# Sheet1.net
KiCad netlist of a schematic drawn in Altium Designer
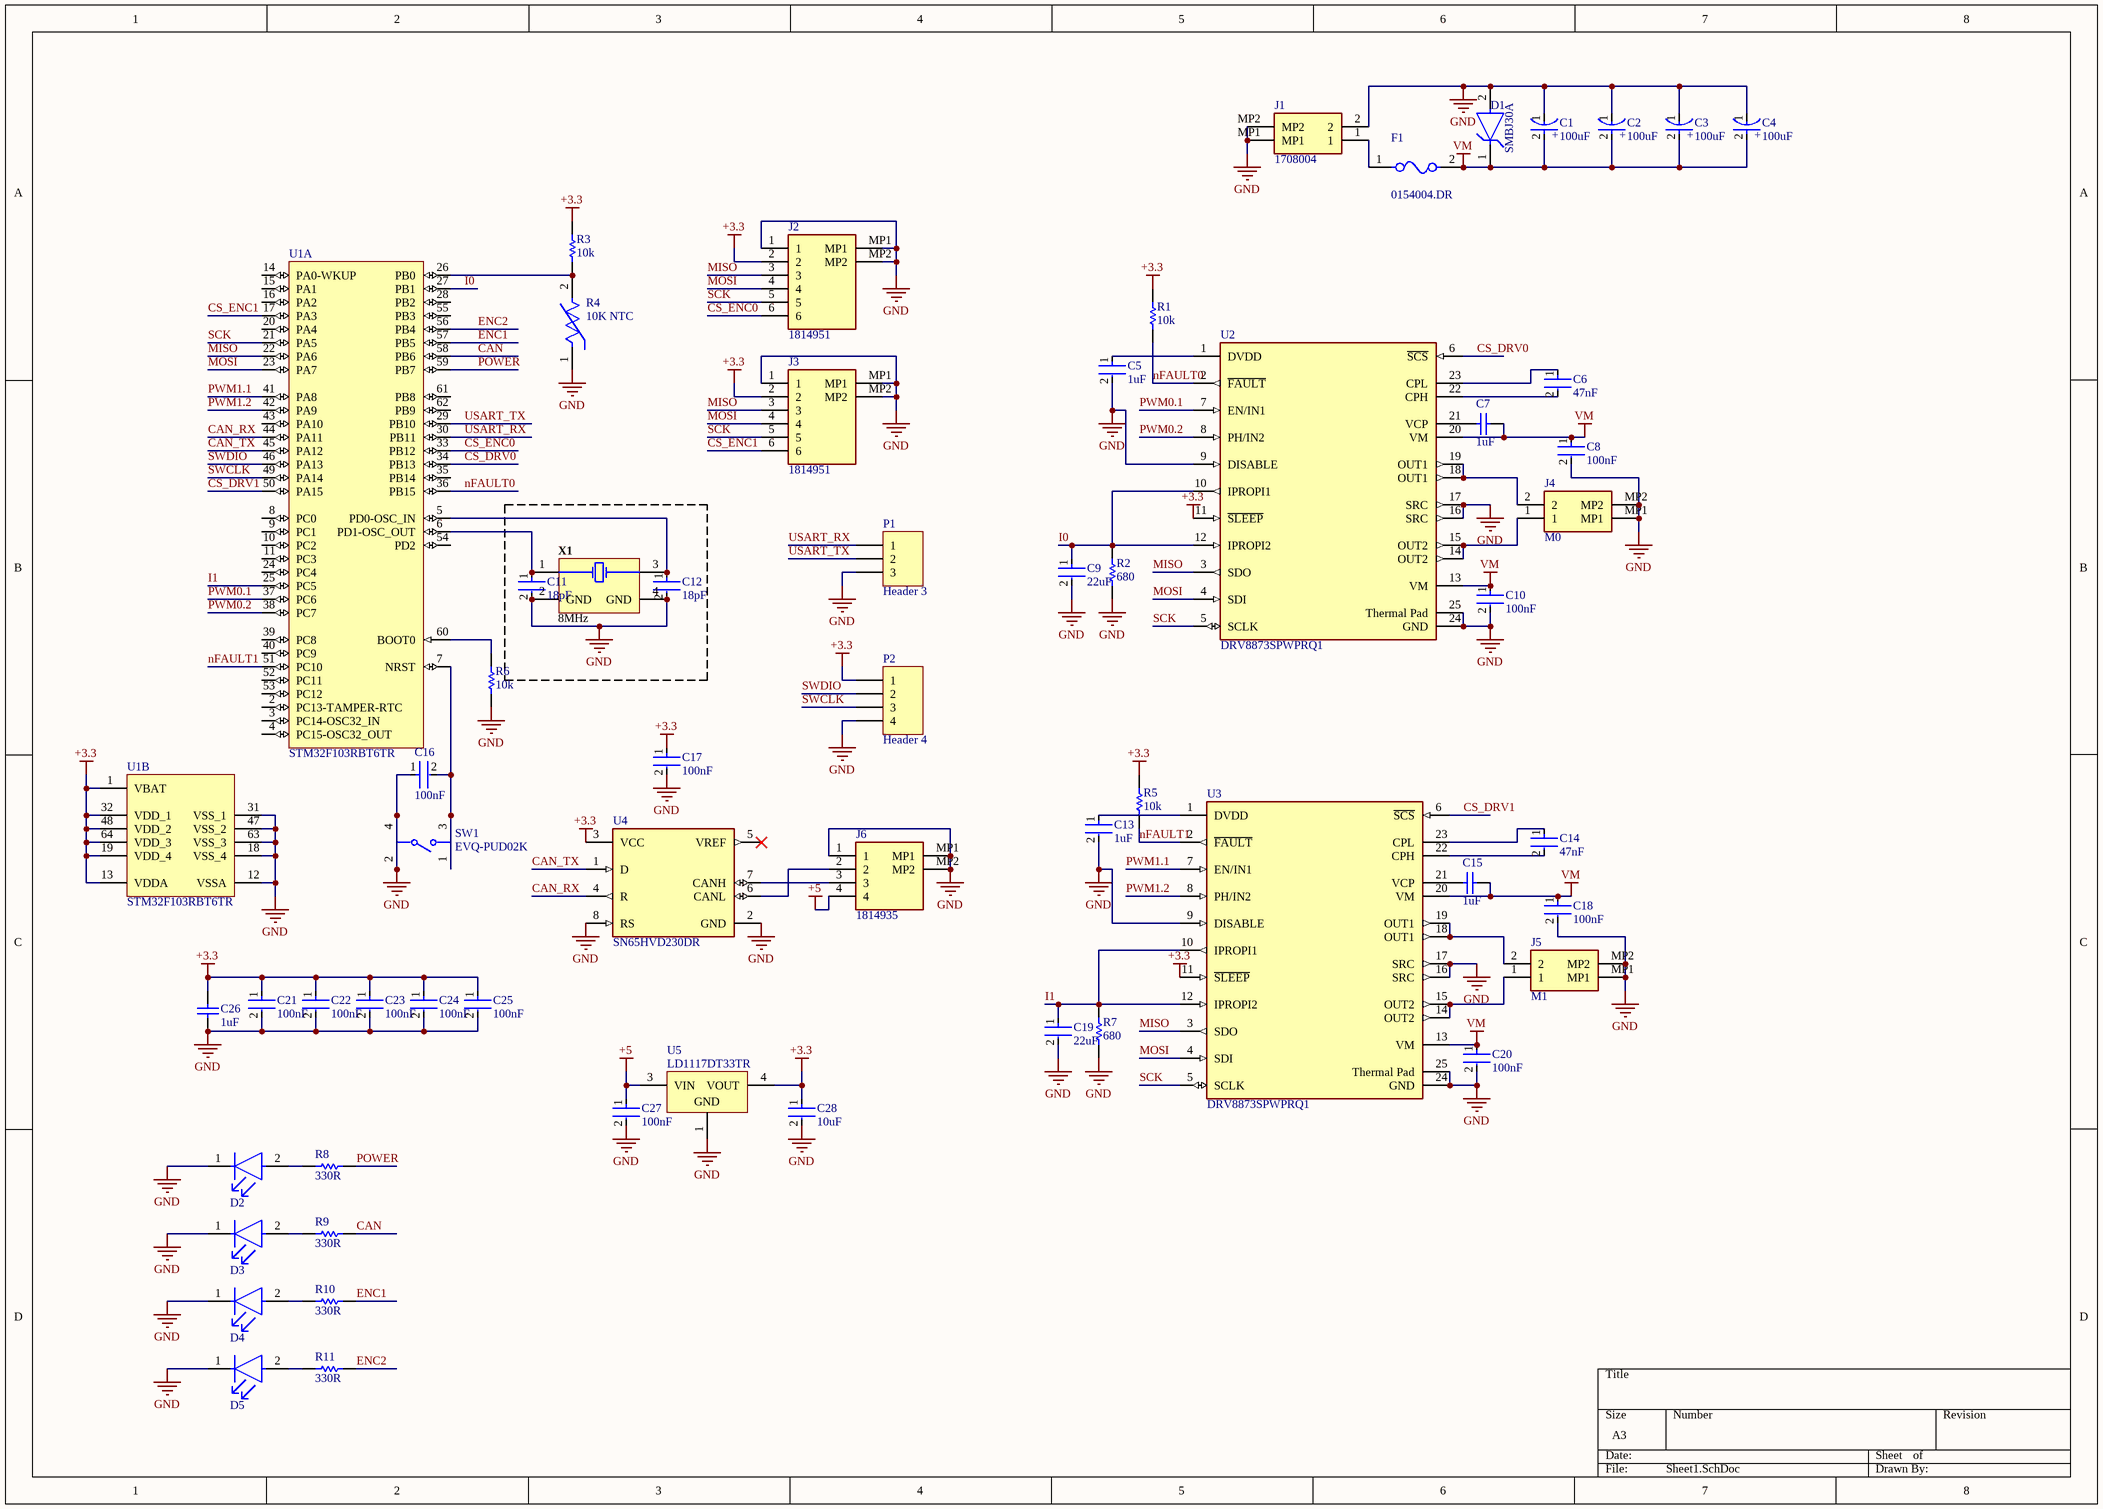
[diagram p0: Sheet1.SchDoc]

(export (version "E")
  (design (tool "Eeschema 10.0.6"))
  (components
    (comp (ref "C1")
      (value "100uF")
      (footprint "FP-FTD-MFG")
      (description "CAP ALUM 100UF 20% 35V SMD")
      (fields (field (name "VOLTAGE") "35V") (field (name "TOLERANCE") "20%"))
      (libsource (lib "Altium Content Vault") (part "a00bbbee19879c290e62620ae7e47b1"))
    )
    (comp (ref "C2")
      (value "100uF")
      (footprint "FP-FTD-MFG")
      (description "CAP ALUM 100UF 20% 35V SMD")
      (fields (field (name "VOLTAGE") "35V") (field (name "TOLERANCE") "20%"))
      (libsource (lib "Altium Content Vault") (part "a00bbbee19879c290e62620ae7e47b1"))
    )
    (comp (ref "C3")
      (value "100uF")
      (footprint "FP-FTD-MFG")
      (description "CAP ALUM 100UF 20% 35V SMD")
      (fields (field (name "VOLTAGE") "35V") (field (name "TOLERANCE") "20%"))
      (libsource (lib "Altium Content Vault") (part "a00bbbee19879c290e62620ae7e47b1"))
    )
    (comp (ref "C4")
      (value "100uF")
      (footprint "FP-FTD-MFG")
      (description "CAP ALUM 100UF 20% 35V SMD")
      (fields (field (name "VOLTAGE") "35V") (field (name "TOLERANCE") "20%"))
      (libsource (lib "Altium Content Vault") (part "a00bbbee19879c290e62620ae7e47b1"))
    )
    (comp (ref "C5")
      (value "1uF")
      (footprint "FP-0805-L_2_01_0_2-W_1_25-IPC_B")
      (description "General Purpose Ceramic Capacitor, 0805, 100nF, 10%, X7R, 15%, 100V")
      (fields (field (name "VOLTAGE") "100V") (field (name "TOLERANCE") "10%"))
      (libsource (lib "Altium Content Vault") (part "b4654b650e69147ec39a6b967a45e02"))
    )
    (comp (ref "C6")
      (value "47nF")
      (footprint "FP-C0805C-DN-IPC_A")
      (description "CAP CER 0.047UF 50V X7R 0805")
      (fields
        (field (name "MANUFACTURER PART NUMBER") "C0805C473K5RACTU")
        (field (name "OCTOPART") "https://octopart.com/c0805c473k5ractu-kemet-138387")
      )
      (libsource (lib "Altium Content Vault") (part "b4654b650e69147ec39a6b967a45e02"))
    )
    (comp (ref "C7")
      (value "1uF")
      (footprint "CAPC2013X145X50ML20T25")
      (fields (field (name "MANUFACTURER") "Kemet") (field (name "PART NUMBER") "C0805C105K4PACTU"))
      (libsource (lib "Altium Content Vault") (part "CAP"))
    )
    (comp (ref "C8")
      (value "100nF")
      (footprint "FP-0805-L_2_01_0_2-W_1_25-MFG")
      (description "General Purpose Ceramic Capacitor, 0805, 100nF, 10%, X7R, 15%, 100V")
      (fields (field (name "VOLTAGE") "100V") (field (name "TOLERANCE") "10%"))
      (libsource (lib "Altium Content Vault") (part "b4654b650e69147ec39a6b967a45e02"))
    )
    (comp (ref "C9")
      (value "22uF")
      (footprint "FP-0805-L_2_01_0_2-W_1_25-IPC_B")
      (description "General Purpose Ceramic Capacitor, 0805, 100nF, 10%, X7R, 15%, 100V")
      (fields (field (name "VOLTAGE") "100V") (field (name "TOLERANCE") "10%"))
      (libsource (lib "Altium Content Vault") (part "b4654b650e69147ec39a6b967a45e02"))
    )
    (comp (ref "C10")
      (value "100nF")
      (footprint "FP-0805-L_2_01_0_2-W_1_25-MFG")
      (description "General Purpose Ceramic Capacitor, 0805, 100nF, 10%, X7R, 15%, 100V")
      (fields (field (name "VOLTAGE") "100V") (field (name "TOLERANCE") "10%"))
      (libsource (lib "Altium Content Vault") (part "b4654b650e69147ec39a6b967a45e02"))
    )
    (comp (ref "C11")
      (value "18pF")
      (footprint "FP-C0603C-CF-MFG")
      (description "CAP CER 18PF 100V 5% NP0 0603")
      (fields (field (name "TOLERANCE") "0.05") (field (name "MANUFACTURER") "KEMET"))
      (libsource (lib "Altium Content Vault") (part "b4654b650e69147ec39a6b967a45e02"))
    )
    (comp (ref "C12")
      (value "18pF")
      (footprint "FP-C0603C-CF-MFG")
      (description "CAP CER 18PF 100V 5% NP0 0603")
      (fields (field (name "TOLERANCE") "0.05") (field (name "MANUFACTURER") "KEMET"))
      (libsource (lib "Altium Content Vault") (part "b4654b650e69147ec39a6b967a45e02"))
    )
    (comp (ref "C13")
      (value "1uF")
      (footprint "FP-0805-L_2_01_0_2-W_1_25-IPC_B")
      (description "General Purpose Ceramic Capacitor, 0805, 100nF, 10%, X7R, 15%, 100V")
      (fields (field (name "VOLTAGE") "100V") (field (name "TOLERANCE") "10%"))
      (libsource (lib "Altium Content Vault") (part "b4654b650e69147ec39a6b967a45e02"))
    )
    (comp (ref "C14")
      (value "47nF")
      (footprint "FP-C0805C-DN-IPC_A")
      (description "CAP CER 0.047UF 50V X7R 0805")
      (fields
        (field (name "MANUFACTURER PART NUMBER") "C0805C473K5RACTU")
        (field (name "OCTOPART") "https://octopart.com/c0805c473k5ractu-kemet-138387")
      )
      (libsource (lib "Altium Content Vault") (part "b4654b650e69147ec39a6b967a45e02"))
    )
    (comp (ref "C15")
      (value "1uF")
      (footprint "CAPC2013X145X50ML20T25")
      (fields (field (name "MANUFACTURER") "Kemet") (field (name "PART NUMBER") "C0805C105K4PACTU"))
      (libsource (lib "Altium Content Vault") (part "CAP"))
    )
    (comp (ref "C16")
      (value "100nF")
      (footprint "FP-0805-L_2_01_0_2-W_1_25-IPC_B")
      (description "General Purpose Ceramic Capacitor, 0805, 100nF, 10%, X7R, 15%, 100V")
      (fields (field (name "VOLTAGE") "100V") (field (name "TOLERANCE") "10%"))
      (libsource (lib "Altium Content Vault") (part "b4654b650e69147ec39a6b967a45e02"))
    )
    (comp (ref "C17")
      (value "100nF")
      (footprint "FP-0805-L_2_01_0_2-W_1_25-MFG")
      (description "General Purpose Ceramic Capacitor, 0805, 100nF, 10%, X7R, 15%, 100V")
      (fields (field (name "VOLTAGE") "100V") (field (name "TOLERANCE") "10%"))
      (libsource (lib "Altium Content Vault") (part "b4654b650e69147ec39a6b967a45e02"))
    )
    (comp (ref "C18")
      (value "100nF")
      (footprint "FP-0805-L_2_01_0_2-W_1_25-MFG")
      (description "General Purpose Ceramic Capacitor, 0805, 100nF, 10%, X7R, 15%, 100V")
      (fields (field (name "VOLTAGE") "100V") (field (name "TOLERANCE") "10%"))
      (libsource (lib "Altium Content Vault") (part "b4654b650e69147ec39a6b967a45e02"))
    )
    (comp (ref "C19")
      (value "22uF")
      (footprint "FP-0805-L_2_01_0_2-W_1_25-IPC_B")
      (description "General Purpose Ceramic Capacitor, 0805, 100nF, 10%, X7R, 15%, 100V")
      (fields (field (name "VOLTAGE") "100V") (field (name "TOLERANCE") "10%"))
      (libsource (lib "Altium Content Vault") (part "b4654b650e69147ec39a6b967a45e02"))
    )
    (comp (ref "C20")
      (value "100nF")
      (footprint "FP-0805-L_2_01_0_2-W_1_25-MFG")
      (description "General Purpose Ceramic Capacitor, 0805, 100nF, 10%, X7R, 15%, 100V")
      (fields (field (name "VOLTAGE") "100V") (field (name "TOLERANCE") "10%"))
      (libsource (lib "Altium Content Vault") (part "b4654b650e69147ec39a6b967a45e02"))
    )
    (comp (ref "C21")
      (value "100nF")
      (footprint "FP-0805-L_2_01_0_2-W_1_25-IPC_B")
      (description "General Purpose Ceramic Capacitor, 0805, 100nF, 10%, X7R, 15%, 100V")
      (fields (field (name "VOLTAGE") "100V") (field (name "TOLERANCE") "10%"))
      (libsource (lib "Altium Content Vault") (part "b4654b650e69147ec39a6b967a45e02"))
    )
    (comp (ref "C22")
      (value "100nF")
      (footprint "FP-0805-L_2_01_0_2-W_1_25-IPC_B")
      (description "General Purpose Ceramic Capacitor, 0805, 100nF, 10%, X7R, 15%, 100V")
      (fields (field (name "VOLTAGE") "100V") (field (name "TOLERANCE") "10%"))
      (libsource (lib "Altium Content Vault") (part "b4654b650e69147ec39a6b967a45e02"))
    )
    (comp (ref "C23")
      (value "100nF")
      (footprint "FP-0805-L_2_01_0_2-W_1_25-IPC_B")
      (description "General Purpose Ceramic Capacitor, 0805, 100nF, 10%, X7R, 15%, 100V")
      (fields (field (name "VOLTAGE") "100V") (field (name "TOLERANCE") "10%"))
      (libsource (lib "Altium Content Vault") (part "b4654b650e69147ec39a6b967a45e02"))
    )
    (comp (ref "C24")
      (value "100nF")
      (footprint "FP-0805-L_2_01_0_2-W_1_25-IPC_B")
      (description "General Purpose Ceramic Capacitor, 0805, 100nF, 10%, X7R, 15%, 100V")
      (fields (field (name "VOLTAGE") "100V") (field (name "TOLERANCE") "10%"))
      (libsource (lib "Altium Content Vault") (part "b4654b650e69147ec39a6b967a45e02"))
    )
    (comp (ref "C25")
      (value "100nF")
      (footprint "FP-0805-L_2_01_0_2-W_1_25-IPC_B")
      (description "General Purpose Ceramic Capacitor, 0805, 100nF, 10%, X7R, 15%, 100V")
      (fields (field (name "VOLTAGE") "100V") (field (name "TOLERANCE") "10%"))
      (libsource (lib "Altium Content Vault") (part "b4654b650e69147ec39a6b967a45e02"))
    )
    (comp (ref "C26")
      (value "1uF")
      (footprint "CAPC2013X145X50ML20T25")
      (fields (field (name "MANUFACTURER") "Kemet") (field (name "PART NUMBER") "C0805C105K4PACTU"))
      (libsource (lib "Altium Content Vault") (part "CAP"))
    )
    (comp (ref "C27")
      (value "100nF")
      (footprint "FP-0805-L_2_01_0_2-W_1_25-IPC_B")
      (description "General Purpose Ceramic Capacitor, 0805, 100nF, 10%, X7R, 15%, 100V")
      (fields (field (name "VOLTAGE") "100V") (field (name "TOLERANCE") "10%"))
      (libsource (lib "Altium Content Vault") (part "b4654b650e69147ec39a6b967a45e02"))
    )
    (comp (ref "C28")
      (value "10uF")
      (footprint "FP-C0805C-DG-IPC_B")
      (description "CAP CER 10UF 10V X5R 0805")
      (fields (field (name "TOLERANCE") "10%") (field (name "MANUFACTURER PART NUMBER") "C0805C106K8PACTU"))
      (libsource (lib "Altium Content Vault") (part "11868f565c42a9108669ba33697ecf6"))
    )
    (comp (ref "D1")
      (value "SMBJ30A")
      (footprint "FP-SMBJ30A-E3-52-0")
      (description "TVS DIODE 30VWM 48.4VC DO214AA")
      (libsource (lib "Altium Content Vault") (part "d9da4cfb8af32e832502365dfa3d88e"))
    )
    (comp (ref "D2")
      (value "TLLG4401")
      (footprint "FP-6_544-5255_01-4-MFG")
      (description "TLLG4401 LED, Green, 2mcd, 3mmDia., T-1, +/-25deg, 565nm, 7mA, 1.9V Vf, 20V Vr, 20mW, -40")
      (libsource (lib "Altium Content Vault") (part "8706943c75ba83719d021d2fdc84c58"))
    )
    (comp (ref "D3")
      (value "TLLG4401")
      (footprint "FP-6_544-5255_01-4-MFG")
      (description "TLLG4401 LED, Green, 2mcd, 3mmDia., T-1, +/-25deg, 565nm, 7mA, 1.9V Vf, 20V Vr, 20mW, -40")
      (libsource (lib "Altium Content Vault") (part "8706943c75ba83719d021d2fdc84c58"))
    )
    (comp (ref "D4")
      (value "TLLG4401")
      (footprint "FP-6_544-5255_01-4-MFG")
      (description "TLLG4401 LED, Green, 2mcd, 3mmDia., T-1, +/-25deg, 565nm, 7mA, 1.9V Vf, 20V Vr, 20mW, -40")
      (libsource (lib "Altium Content Vault") (part "8706943c75ba83719d021d2fdc84c58"))
    )
    (comp (ref "D5")
      (value "TLLG4401")
      (footprint "FP-6_544-5255_01-4-MFG")
      (description "TLLG4401 LED, Green, 2mcd, 3mmDia., T-1, +/-25deg, 565nm, 7mA, 1.9V Vf, 20V Vr, 20mW, -40")
      (libsource (lib "Altium Content Vault") (part "8706943c75ba83719d021d2fdc84c58"))
    )
    (comp (ref "F1")
      (value "0154004.DR")
      (footprint "FP-0154-MFG")
      (description "FUSE BRD MNT 4A 125VAC/VDC 2SMD")
      (fields
        (field (name "MANUFACTURER") "Littelfuse")
        (field (name "OCTOPART") "https://octopart.com/0154004.dr-littelfuse-565861")
      )
      (libsource (lib "Altium Content Vault") (part "5bcf9b9f640e542cf0359d10258e979"))
    )
    (comp (ref "J1")
      (value "1708004")
      (footprint "1708004")
      (description "Pluggable Terminal Blocks PTSM 0,5/ 2-HH- 2,5-SMD WH R32")
      (fields (field (name "MOUSER PART NUMBER") "651-1708004"))
      (libsource (lib "1708004") (part "1708004"))
    )
    (comp (ref "J2")
      (value "1814951")
      (footprint "1814951")
      (description "Pluggable Terminal Blocks PTSM 0,5/ 6-HH0-2,5- SMD WH R44")
      (libsource (lib "1814951") (part "1814951"))
    )
    (comp (ref "J3")
      (value "1814951")
      (footprint "1814951")
      (description "Pluggable Terminal Blocks PTSM 0,5/ 6-HH0-2,5- SMD WH R44")
      (libsource (lib "1814951") (part "1814951"))
    )
    (comp (ref "J4")
      (value "M0")
      (footprint "1815125")
      (description "Phoenix Contact PTSM Series, 2.5mm Pitch Printed Circuit Board Connector, 6A")
      (fields
        (field (name "MOUSER PART NUMBER") "651-1815125")
        (field (name "MANUFACTURER_PART_NUMBER") "1815125")
      )
      (libsource (lib "1815125") (part "1815125"))
    )
    (comp (ref "J5")
      (value "M1")
      (footprint "1815125")
      (description "Phoenix Contact PTSM Series, 2.5mm Pitch Printed Circuit Board Connector, 6A")
      (fields
        (field (name "MOUSER PART NUMBER") "651-1815125")
        (field (name "MANUFACTURER_PART_NUMBER") "1815125")
      )
      (libsource (lib "1815125") (part "1815125"))
    )
    (comp (ref "J6")
      (value "1814935")
      (footprint "1814935")
      (description "Pluggable Terminal Blocks PTSM 0,5/ 4-HH0-2,5- SMD WH R32")
      (libsource (lib "1814935") (part "1814935"))
    )
    (comp (ref "P1")
      (value "Header 3")
      (footprint "HDR1X3")
      (description "Header, 3-Pin")
      (fields (field (name "PUBLISHER") "Altium Limited"))
      (libsource (lib "Miscellaneous Connectors") (part "Header 3"))
    )
    (comp (ref "P2")
      (value "Header 4")
      (footprint "HDR1X4")
      (description "Header, 4-Pin")
      (fields (field (name "PUBLISHER") "Altium Limited"))
      (libsource (lib "Miscellaneous Connectors") (part "Header 4"))
    )
    (comp (ref "R1")
      (value "10k")
      (footprint "RESC2013X60X35NL10T20")
      (description "Chip Resistor, 10 KOhm, +/- 1%, 0.125 W, -55 to 155 degC, 0805 (2012 Metric), RoHS, Tape and Reel")
      (fields (field (name "MANUFACTURER") "Yageo"))
      (libsource (lib "Altium Content Vault") (part "RES-2"))
    )
    (comp (ref "R2")
      (value "680")
      (footprint "RESC2013X60X35NL10T20")
      (description "Chip Resistor, 10 KOhm, +/- 1%, 0.125 W, -55 to 155 degC, 0805 (2012 Metric), RoHS, Tape and Reel")
      (fields (field (name "MANUFACTURER") "Yageo"))
      (libsource (lib "Altium Content Vault") (part "RES-2"))
    )
    (comp (ref "R3")
      (value "10k")
      (footprint "RESC2013X60X35ML10T20")
      (fields (field (name "TOLERANCE") "5%") (field (name "MANUFACTURER") "Yageo"))
      (libsource (lib "Altium Content Vault") (part "RES-2"))
    )
    (comp (ref "R4")
      (value "10K NTC")
      (footprint "FP-NCP18-0_15-IPC_A")
      (description "NTC Thermistor for Temperature Sensor, 0603, 10kΩ, 1%, 0.1mA, 5V")
      (fields (field (name "TOLERANCE") "1%"))
      (libsource (lib "Altium Content Vault") (part "3b148a6ebabc5fb4d708a66c052d352"))
    )
    (comp (ref "R5")
      (value "10k")
      (footprint "RESC2013X60X35NL10T20")
      (description "Chip Resistor, 10 KOhm, +/- 1%, 0.125 W, -55 to 155 degC, 0805 (2012 Metric), RoHS, Tape and Reel")
      (fields (field (name "MANUFACTURER") "Yageo"))
      (libsource (lib "Altium Content Vault") (part "RES-2"))
    )
    (comp (ref "R6")
      (value "10k")
      (footprint "RESC2013X60X35ML10T20")
      (fields (field (name "TOLERANCE") "5%") (field (name "MANUFACTURER") "Yageo"))
      (libsource (lib "Altium Content Vault") (part "RES-2"))
    )
    (comp (ref "R7")
      (value "680")
      (footprint "RESC2013X60X35NL10T20")
      (description "Chip Resistor, 10 KOhm, +/- 1%, 0.125 W, -55 to 155 degC, 0805 (2012 Metric), RoHS, Tape and Reel")
      (fields (field (name "MANUFACTURER") "Yageo"))
      (libsource (lib "Altium Content Vault") (part "RES-2"))
    )
    (comp (ref "R8")
      (value "330R")
      (footprint "RESC2013X60X35ML10T20")
      (description "Chip Resistor, 1 KOhm, +/- 1%, 125 mW, -55 to 155 degC, 0805 (2012 Metric), RoHS, Tape and Reel")
      (fields (field (name "TOLERANCE") "1%") (field (name "MANUFACTURER") "Yageo"))
      (libsource (lib "Altium Content Vault") (part "RES-2"))
    )
    (comp (ref "R9")
      (value "330R")
      (footprint "RESC2013X60X35ML10T20")
      (description "Chip Resistor, 1 KOhm, +/- 1%, 125 mW, -55 to 155 degC, 0805 (2012 Metric), RoHS, Tape and Reel")
      (fields (field (name "TOLERANCE") "1%") (field (name "MANUFACTURER") "Yageo"))
      (libsource (lib "Altium Content Vault") (part "RES-2"))
    )
    (comp (ref "R10")
      (value "330R")
      (footprint "RESC2013X60X35ML10T20")
      (description "Chip Resistor, 1 KOhm, +/- 1%, 125 mW, -55 to 155 degC, 0805 (2012 Metric), RoHS, Tape and Reel")
      (fields (field (name "TOLERANCE") "1%") (field (name "MANUFACTURER") "Yageo"))
      (libsource (lib "Altium Content Vault") (part "RES-2"))
    )
    (comp (ref "R11")
      (value "330R")
      (footprint "RESC2013X60X35ML10T20")
      (description "Chip Resistor, 1 KOhm, +/- 1%, 125 mW, -55 to 155 degC, 0805 (2012 Metric), RoHS, Tape and Reel")
      (fields (field (name "TOLERANCE") "1%") (field (name "MANUFACTURER") "Yageo"))
      (libsource (lib "Altium Content Vault") (part "RES-2"))
    )
    (comp (ref "SW1")
      (value "EVQ-PUD02K")
      (footprint "FP-EVQ-PUD02K-MFG")
      (description "SWITCH TACTILE SPST-NO 0.05A 12V")
      (libsource (lib "Altium Content Vault") (part "98412ef6bd26695bde79fccaf8fa8e7"))
    )
    (comp (ref "U1")
      (value "STM32F103RBT6TR")
      (footprint "STM-LQFP64_V")
      (libsource (lib "Altium Content Vault") (part "MC-ARM-STM32F103X8_B-SQ64"))
    )
    (comp (ref "U2")
      (value "DRV8873SPWPRQ1")
      (footprint "FP-PWP0024J-MFG")
      (description "IC MTRDRV UNIPLR 0-5.5V 24HTSSOP")
      (libsource (lib "Altium Content Vault") (part "639cfc0396780f9562c68c0b1c9b09f"))
    )
    (comp (ref "U3")
      (value "DRV8873SPWPRQ1")
      (footprint "FP-PWP0024J-MFG")
      (description "IC MTRDRV UNIPLR 0-5.5V 24HTSSOP")
      (libsource (lib "Altium Content Vault") (part "639cfc0396780f9562c68c0b1c9b09f"))
    )
    (comp (ref "U4")
      (value "SN65HVD230DR")
      (footprint "FP-D0008A-IPC_A")
      (description "IC TRANSCEIVER HALF 1/1 8SOIC")
      (libsource (lib "Altium Content Vault") (part "43b56812b1adf0e60a7acfb7c27ab91"))
    )
    (comp (ref "U5")
      (value "LD1117DT33TR")
      (footprint "TO-252_M")
      (description "Fixed Low Drop Positive Voltage Regulator, 3.3V, 3-Pin DPAK, Tape and Reel")
      (libsource (lib "Altium Content Vault") (part "PM-REG-LD1117-SOT3"))
    )
    (comp (ref "X1")
      (value "8MHz")
      (footprint "TXC-7B-4_V")
      (description "SMD Seam Sealing Crystal, 8 MHz, +/- 30 ppm, 18 pF, -10 to 70 degC, 4-Pin SMD, RoHS, Tape and Reel")
      (fields (field (name "TOLERANCE") "1%"))
      (libsource (lib "Altium Content Vault") (part "XTAL-1-3-4"))
    )
  )
  (nets
    (net (code "1") (name "+3.3") (class "Default")
      (node (ref "C17") (pin "1") (pinfunction "1_1") (pintype "passive"))
      (node (ref "C21") (pin "1") (pinfunction "1_1") (pintype "passive"))
      (node (ref "C22") (pin "1") (pinfunction "1_1") (pintype "passive"))
      (node (ref "C23") (pin "1") (pinfunction "1_1") (pintype "passive"))
      (node (ref "C24") (pin "1") (pinfunction "1_1") (pintype "passive"))
      (node (ref "C25") (pin "1") (pinfunction "1_1") (pintype "passive"))
      (node (ref "C26") (pin "2") (pinfunction "2_2") (pintype "passive"))
      (node (ref "C28") (pin "1") (pinfunction "1_1") (pintype "passive"))
      (node (ref "J2") (pin "2") (pinfunction "2_2") (pintype "passive"))
      (node (ref "J3") (pin "2") (pinfunction "2_2") (pintype "passive"))
      (node (ref "P2") (pin "1") (pinfunction "1_1") (pintype "passive"))
      (node (ref "R1") (pin "2") (pinfunction "2_2") (pintype "passive"))
      (node (ref "R3") (pin "2") (pinfunction "2_2") (pintype "passive"))
      (node (ref "R5") (pin "2") (pinfunction "2_2") (pintype "passive"))
      (node (ref "U1") (pin "1") (pinfunction "VBAT_1") (pintype "power_in"))
      (node (ref "U1") (pin "13") (pinfunction "VDDA_13") (pintype "power_in"))
      (node (ref "U1") (pin "19") (pinfunction "VDD_4_19") (pintype "power_in"))
      (node (ref "U1") (pin "32") (pinfunction "VDD_1_32") (pintype "power_in"))
      (node (ref "U1") (pin "48") (pinfunction "VDD_2_48") (pintype "power_in"))
      (node (ref "U1") (pin "64") (pinfunction "VDD_3_64") (pintype "power_in"))
      (node (ref "U2") (pin "11") (pinfunction "~{SLEEP}_11") (pintype "input"))
      (node (ref "U3") (pin "11") (pinfunction "~{SLEEP}_11") (pintype "input"))
      (node (ref "U4") (pin "3") (pinfunction "VCC_3") (pintype "power_in"))
      (node (ref "U5") (pin "4") (pinfunction "VOUT_4") (pintype "power_in"))
    )
    (net (code "2") (name "+5") (class "Default")
      (node (ref "C27") (pin "1") (pinfunction "1_1") (pintype "passive"))
      (node (ref "J6") (pin "4") (pinfunction "4_4") (pintype "passive"))
      (node (ref "U5") (pin "3") (pinfunction "VIN_3") (pintype "power_in"))
    )
    (net (code "3") (name "/CAN") (class "Default")
      (node (ref "R9") (pin "1") (pinfunction "1_1") (pintype "passive"))
      (node (ref "U1") (pin "58") (pinfunction "PB6_58") (pintype "bidirectional"))
    )
    (net (code "4") (name "/CAN_RX") (class "Default")
      (node (ref "U1") (pin "44") (pinfunction "PA11_44") (pintype "bidirectional"))
      (node (ref "U4") (pin "4") (pinfunction "R_4") (pintype "output"))
    )
    (net (code "5") (name "/CAN_TX") (class "Default")
      (node (ref "U1") (pin "45") (pinfunction "PA12_45") (pintype "bidirectional"))
      (node (ref "U4") (pin "1") (pinfunction "D_1") (pintype "input"))
    )
    (net (code "6") (name "/CS_DRV0") (class "Default")
      (node (ref "U1") (pin "34") (pinfunction "PB13_34") (pintype "bidirectional"))
      (node (ref "U2") (pin "6") (pinfunction "~{SCS}_6") (pintype "input"))
    )
    (net (code "7") (name "/CS_DRV1") (class "Default")
      (node (ref "U1") (pin "50") (pinfunction "PA15_50") (pintype "bidirectional"))
      (node (ref "U3") (pin "6") (pinfunction "~{SCS}_6") (pintype "input"))
    )
    (net (code "8") (name "/CS_ENC0") (class "Default")
      (node (ref "J2") (pin "6") (pinfunction "6_6") (pintype "passive"))
      (node (ref "U1") (pin "33") (pinfunction "PB12_33") (pintype "bidirectional"))
    )
    (net (code "9") (name "/CS_ENC1") (class "Default")
      (node (ref "J3") (pin "6") (pinfunction "6_6") (pintype "passive"))
      (node (ref "U1") (pin "17") (pinfunction "PA3_17") (pintype "bidirectional"))
    )
    (net (code "10") (name "/ENC1") (class "Default")
      (node (ref "R10") (pin "1") (pinfunction "1_1") (pintype "passive"))
      (node (ref "U1") (pin "57") (pinfunction "PB5_57") (pintype "bidirectional"))
    )
    (net (code "11") (name "/ENC2") (class "Default")
      (node (ref "R11") (pin "1") (pinfunction "1_1") (pintype "passive"))
      (node (ref "U1") (pin "56") (pinfunction "PB4_56") (pintype "bidirectional"))
    )
    (net (code "12") (name "/I0") (class "Default")
      (node (ref "C9") (pin "1") (pinfunction "1_1") (pintype "passive"))
      (node (ref "R2") (pin "2") (pinfunction "2_2") (pintype "passive"))
      (node (ref "U1") (pin "27") (pinfunction "PB1_27") (pintype "bidirectional"))
      (node (ref "U2") (pin "10") (pinfunction "IPROPI1_10") (pintype "output"))
      (node (ref "U2") (pin "12") (pinfunction "IPROPI2_12") (pintype "input"))
    )
    (net (code "13") (name "/I1") (class "Default")
      (node (ref "C19") (pin "1") (pinfunction "1_1") (pintype "passive"))
      (node (ref "R7") (pin "2") (pinfunction "2_2") (pintype "passive"))
      (node (ref "U1") (pin "25") (pinfunction "PC5_25") (pintype "bidirectional"))
      (node (ref "U3") (pin "10") (pinfunction "IPROPI1_10") (pintype "output"))
      (node (ref "U3") (pin "12") (pinfunction "IPROPI2_12") (pintype "input"))
    )
    (net (code "14") (name "/MISO") (class "Default")
      (node (ref "J2") (pin "3") (pinfunction "3_3") (pintype "passive"))
      (node (ref "J3") (pin "3") (pinfunction "3_3") (pintype "passive"))
      (node (ref "U1") (pin "22") (pinfunction "PA6_22") (pintype "bidirectional"))
      (node (ref "U2") (pin "3") (pinfunction "SDO_3") (pintype "output"))
      (node (ref "U3") (pin "3") (pinfunction "SDO_3") (pintype "output"))
    )
    (net (code "15") (name "/MOSI") (class "Default")
      (node (ref "J2") (pin "4") (pinfunction "4_4") (pintype "passive"))
      (node (ref "J3") (pin "4") (pinfunction "4_4") (pintype "passive"))
      (node (ref "U1") (pin "23") (pinfunction "PA7_23") (pintype "bidirectional"))
      (node (ref "U2") (pin "4") (pinfunction "SDI_4") (pintype "input"))
      (node (ref "U3") (pin "4") (pinfunction "SDI_4") (pintype "input"))
    )
    (net (code "16") (name "/POWER") (class "Default")
      (node (ref "R8") (pin "1") (pinfunction "1_1") (pintype "passive"))
      (node (ref "U1") (pin "59") (pinfunction "PB7_59") (pintype "bidirectional"))
    )
    (net (code "17") (name "/PWM0.1") (class "Default")
      (node (ref "U1") (pin "37") (pinfunction "PC6_37") (pintype "bidirectional"))
      (node (ref "U2") (pin "7") (pinfunction "EN/IN1_7") (pintype "input"))
    )
    (net (code "18") (name "/PWM0.2") (class "Default")
      (node (ref "U1") (pin "38") (pinfunction "PC7_38") (pintype "bidirectional"))
      (node (ref "U2") (pin "8") (pinfunction "PH/IN2_8") (pintype "input"))
    )
    (net (code "19") (name "/PWM1.1") (class "Default")
      (node (ref "U1") (pin "41") (pinfunction "PA8_41") (pintype "bidirectional"))
      (node (ref "U3") (pin "7") (pinfunction "EN/IN1_7") (pintype "input"))
    )
    (net (code "20") (name "/PWM1.2") (class "Default")
      (node (ref "U1") (pin "42") (pinfunction "PA9_42") (pintype "bidirectional"))
      (node (ref "U3") (pin "8") (pinfunction "PH/IN2_8") (pintype "input"))
    )
    (net (code "21") (name "/SCK") (class "Default")
      (node (ref "J2") (pin "5") (pinfunction "5_5") (pintype "passive"))
      (node (ref "J3") (pin "5") (pinfunction "5_5") (pintype "passive"))
      (node (ref "U1") (pin "21") (pinfunction "PA5_21") (pintype "bidirectional"))
      (node (ref "U2") (pin "5") (pinfunction "SCLK_5") (pintype "bidirectional"))
      (node (ref "U3") (pin "5") (pinfunction "SCLK_5") (pintype "bidirectional"))
    )
    (net (code "22") (name "/SWCLK") (class "Default")
      (node (ref "P2") (pin "3") (pinfunction "3_3") (pintype "passive"))
      (node (ref "U1") (pin "49") (pinfunction "PA14_49") (pintype "bidirectional"))
    )
    (net (code "23") (name "/SWDIO") (class "Default")
      (node (ref "P2") (pin "2") (pinfunction "2_2") (pintype "passive"))
      (node (ref "U1") (pin "46") (pinfunction "PA13_46") (pintype "bidirectional"))
    )
    (net (code "24") (name "/USART_RX") (class "Default")
      (node (ref "P1") (pin "1") (pinfunction "1_1") (pintype "passive"))
      (node (ref "U1") (pin "30") (pinfunction "PB11_30") (pintype "bidirectional"))
    )
    (net (code "25") (name "/USART_TX") (class "Default")
      (node (ref "P1") (pin "2") (pinfunction "2_2") (pintype "passive"))
      (node (ref "U1") (pin "29") (pinfunction "PB10_29") (pintype "bidirectional"))
    )
    (net (code "26") (name "/nFAULT0") (class "Default")
      (node (ref "R1") (pin "1") (pinfunction "1_1") (pintype "passive"))
      (node (ref "U1") (pin "36") (pinfunction "PB15_36") (pintype "bidirectional"))
      (node (ref "U2") (pin "2") (pinfunction "~{FAULT}_2") (pintype "output"))
    )
    (net (code "27") (name "/nFAULT1") (class "Default")
      (node (ref "R5") (pin "1") (pinfunction "1_1") (pintype "passive"))
      (node (ref "U1") (pin "51") (pinfunction "PC10_51") (pintype "bidirectional"))
      (node (ref "U3") (pin "2") (pinfunction "~{FAULT}_2") (pintype "output"))
    )
    (net (code "28") (name "GND") (class "Default")
      (node (ref "C1") (pin "1") (pinfunction "C_1") (pintype "passive"))
      (node (ref "C10") (pin "2") (pinfunction "2_2") (pintype "passive"))
      (node (ref "C11") (pin "2") (pinfunction "2_2") (pintype "passive"))
      (node (ref "C12") (pin "2") (pinfunction "2_2") (pintype "passive"))
      (node (ref "C13") (pin "2") (pinfunction "2_2") (pintype "passive"))
      (node (ref "C16") (pin "1") (pinfunction "1_1") (pintype "passive"))
      (node (ref "C17") (pin "2") (pinfunction "2_2") (pintype "passive"))
      (node (ref "C18") (pin "2") (pinfunction "2_2") (pintype "passive"))
      (node (ref "C19") (pin "2") (pinfunction "2_2") (pintype "passive"))
      (node (ref "C2") (pin "1") (pinfunction "C_1") (pintype "passive"))
      (node (ref "C20") (pin "2") (pinfunction "2_2") (pintype "passive"))
      (node (ref "C21") (pin "2") (pinfunction "2_2") (pintype "passive"))
      (node (ref "C22") (pin "2") (pinfunction "2_2") (pintype "passive"))
      (node (ref "C23") (pin "2") (pinfunction "2_2") (pintype "passive"))
      (node (ref "C24") (pin "2") (pinfunction "2_2") (pintype "passive"))
      (node (ref "C25") (pin "2") (pinfunction "2_2") (pintype "passive"))
      (node (ref "C26") (pin "1") (pinfunction "1_1") (pintype "passive"))
      (node (ref "C27") (pin "2") (pinfunction "2_2") (pintype "passive"))
      (node (ref "C28") (pin "2") (pinfunction "2_2") (pintype "passive"))
      (node (ref "C3") (pin "1") (pinfunction "C_1") (pintype "passive"))
      (node (ref "C4") (pin "1") (pinfunction "C_1") (pintype "passive"))
      (node (ref "C5") (pin "2") (pinfunction "2_2") (pintype "passive"))
      (node (ref "C8") (pin "2") (pinfunction "2_2") (pintype "passive"))
      (node (ref "C9") (pin "2") (pinfunction "2_2") (pintype "passive"))
      (node (ref "D1") (pin "2") (pinfunction "A_2") (pintype "passive"))
      (node (ref "D2") (pin "1") (pinfunction "C_1") (pintype "passive"))
      (node (ref "D3") (pin "1") (pinfunction "C_1") (pintype "passive"))
      (node (ref "D4") (pin "1") (pinfunction "C_1") (pintype "passive"))
      (node (ref "D5") (pin "1") (pinfunction "C_1") (pintype "passive"))
      (node (ref "J1") (pin "2") (pinfunction "2_2") (pintype "passive"))
      (node (ref "J1") (pin "MP1") (pinfunction "MP1_MP1") (pintype "passive"))
      (node (ref "J1") (pin "MP2") (pinfunction "MP2_MP2") (pintype "passive"))
      (node (ref "J2") (pin "1") (pinfunction "1_1") (pintype "passive"))
      (node (ref "J2") (pin "MP1") (pinfunction "MP1_MP1") (pintype "passive"))
      (node (ref "J2") (pin "MP2") (pinfunction "MP2_MP2") (pintype "passive"))
      (node (ref "J3") (pin "1") (pinfunction "1_1") (pintype "passive"))
      (node (ref "J3") (pin "MP1") (pinfunction "MP1_MP1") (pintype "passive"))
      (node (ref "J3") (pin "MP2") (pinfunction "MP2_MP2") (pintype "passive"))
      (node (ref "J4") (pin "MP1") (pinfunction "MP1_MP1") (pintype "passive"))
      (node (ref "J4") (pin "MP2") (pinfunction "MP2_MP2") (pintype "passive"))
      (node (ref "J5") (pin "MP1") (pinfunction "MP1_MP1") (pintype "passive"))
      (node (ref "J5") (pin "MP2") (pinfunction "MP2_MP2") (pintype "passive"))
      (node (ref "J6") (pin "1") (pinfunction "1_1") (pintype "passive"))
      (node (ref "J6") (pin "MP1") (pinfunction "MP1_MP1") (pintype "passive"))
      (node (ref "J6") (pin "MP2") (pinfunction "MP2_MP2") (pintype "passive"))
      (node (ref "P1") (pin "3") (pinfunction "3_3") (pintype "passive"))
      (node (ref "P2") (pin "4") (pinfunction "4_4") (pintype "passive"))
      (node (ref "R2") (pin "1") (pinfunction "1_1") (pintype "passive"))
      (node (ref "R4") (pin "1") (pinfunction "1_1") (pintype "passive"))
      (node (ref "R6") (pin "1") (pinfunction "1_1") (pintype "passive"))
      (node (ref "R7") (pin "1") (pinfunction "1_1") (pintype "passive"))
      (node (ref "SW1") (pin "2") (pinfunction "2_2") (pintype "passive"))
      (node (ref "SW1") (pin "4") (pinfunction "4_4") (pintype "passive"))
      (node (ref "U1") (pin "12") (pinfunction "VSSA_12") (pintype "power_in"))
      (node (ref "U1") (pin "18") (pinfunction "VSS_4_18") (pintype "power_in"))
      (node (ref "U1") (pin "31") (pinfunction "VSS_1_31") (pintype "power_in"))
      (node (ref "U1") (pin "47") (pinfunction "VSS_2_47") (pintype "power_in"))
      (node (ref "U1") (pin "63") (pinfunction "VSS_3_63") (pintype "power_in"))
      (node (ref "U2") (pin "16") (pinfunction "SRC_16") (pintype "output"))
      (node (ref "U2") (pin "17") (pinfunction "SRC_17") (pintype "output"))
      (node (ref "U2") (pin "24") (pinfunction "GND_24") (pintype "power_in"))
      (node (ref "U2") (pin "25") (pinfunction "Thermal_Pad_25") (pintype "power_in"))
      (node (ref "U2") (pin "9") (pinfunction "DISABLE_9") (pintype "input"))
      (node (ref "U3") (pin "16") (pinfunction "SRC_16") (pintype "output"))
      (node (ref "U3") (pin "17") (pinfunction "SRC_17") (pintype "output"))
      (node (ref "U3") (pin "24") (pinfunction "GND_24") (pintype "power_in"))
      (node (ref "U3") (pin "25") (pinfunction "Thermal_Pad_25") (pintype "power_in"))
      (node (ref "U3") (pin "9") (pinfunction "DISABLE_9") (pintype "input"))
      (node (ref "U4") (pin "2") (pinfunction "GND_2") (pintype "power_in"))
      (node (ref "U4") (pin "8") (pinfunction "RS_8") (pintype "input"))
      (node (ref "U5") (pin "1") (pinfunction "GND_1") (pintype "power_in"))
      (node (ref "X1") (pin "2") (pinfunction "GND_2") (pintype "power_in"))
      (node (ref "X1") (pin "4") (pinfunction "GND_4") (pintype "power_in"))
    )
    (net (code "29") (name "Net-(D2-A)") (class "Default")
      (node (ref "D2") (pin "2") (pinfunction "A_2") (pintype "passive"))
      (node (ref "R8") (pin "2") (pinfunction "2_2") (pintype "passive"))
    )
    (net (code "30") (name "Net-(D3-A)") (class "Default")
      (node (ref "D3") (pin "2") (pinfunction "A_2") (pintype "passive"))
      (node (ref "R9") (pin "2") (pinfunction "2_2") (pintype "passive"))
    )
    (net (code "31") (name "Net-(D4-A)") (class "Default")
      (node (ref "D4") (pin "2") (pinfunction "A_2") (pintype "passive"))
      (node (ref "R10") (pin "2") (pinfunction "2_2") (pintype "passive"))
    )
    (net (code "32") (name "Net-(D5-A)") (class "Default")
      (node (ref "D5") (pin "2") (pinfunction "A_2") (pintype "passive"))
      (node (ref "R11") (pin "2") (pinfunction "2_2") (pintype "passive"))
    )
    (net (code "33") (name "Net-(F1-Pad1)") (class "Default")
      (node (ref "F1") (pin "1") (pinfunction "1_1") (pintype "passive"))
      (node (ref "J1") (pin "1") (pinfunction "1_1") (pintype "passive"))
    )
    (net (code "34") (name "Net-(J4-Pad1)") (class "Default")
      (node (ref "J4") (pin "1") (pinfunction "1_1") (pintype "passive"))
      (node (ref "U2") (pin "14") (pinfunction "OUT2_14") (pintype "output"))
      (node (ref "U2") (pin "15") (pinfunction "OUT2_15") (pintype "output"))
    )
    (net (code "35") (name "Net-(J4-Pad2)") (class "Default")
      (node (ref "J4") (pin "2") (pinfunction "2_2") (pintype "passive"))
      (node (ref "U2") (pin "18") (pinfunction "OUT1_18") (pintype "output"))
      (node (ref "U2") (pin "19") (pinfunction "OUT1_19") (pintype "output"))
    )
    (net (code "36") (name "Net-(J5-Pad1)") (class "Default")
      (node (ref "J5") (pin "1") (pinfunction "1_1") (pintype "passive"))
      (node (ref "U3") (pin "14") (pinfunction "OUT2_14") (pintype "output"))
      (node (ref "U3") (pin "15") (pinfunction "OUT2_15") (pintype "output"))
    )
    (net (code "37") (name "Net-(J5-Pad2)") (class "Default")
      (node (ref "J5") (pin "2") (pinfunction "2_2") (pintype "passive"))
      (node (ref "U3") (pin "18") (pinfunction "OUT1_18") (pintype "output"))
      (node (ref "U3") (pin "19") (pinfunction "OUT1_19") (pintype "output"))
    )
    (net (code "38") (name "Net-(U1A-BOOT0)") (class "Default")
      (node (ref "R6") (pin "2") (pinfunction "2_2") (pintype "passive"))
      (node (ref "U1") (pin "60") (pinfunction "BOOT0_60") (pintype "input"))
    )
    (net (code "39") (name "Net-(U1A-NRST)") (class "Default")
      (node (ref "C16") (pin "2") (pinfunction "2_2") (pintype "passive"))
      (node (ref "SW1") (pin "1") (pinfunction "1_1") (pintype "passive"))
      (node (ref "SW1") (pin "3") (pinfunction "3_3") (pintype "passive"))
      (node (ref "U1") (pin "7") (pinfunction "NRST_7") (pintype "bidirectional"))
    )
    (net (code "40") (name "Net-(U1A-PB0)") (class "Default")
      (node (ref "R3") (pin "1") (pinfunction "1_1") (pintype "passive"))
      (node (ref "R4") (pin "2") (pinfunction "2_2") (pintype "passive"))
      (node (ref "U1") (pin "26") (pinfunction "PB0_26") (pintype "bidirectional"))
    )
    (net (code "41") (name "Net-(U1A-PD0-OSC_IN)") (class "Default")
      (node (ref "C12") (pin "1") (pinfunction "1_1") (pintype "passive"))
      (node (ref "U1") (pin "5") (pinfunction "PD0-OSC_IN_5") (pintype "bidirectional"))
      (node (ref "X1") (pin "3") (pinfunction "X2_3") (pintype "passive"))
    )
    (net (code "42") (name "Net-(U1A-PD1-OSC_OUT)") (class "Default")
      (node (ref "C11") (pin "1") (pinfunction "1_1") (pintype "passive"))
      (node (ref "U1") (pin "6") (pinfunction "PD1-OSC_OUT_6") (pintype "bidirectional"))
      (node (ref "X1") (pin "1") (pinfunction "X1_1") (pintype "passive"))
    )
    (net (code "43") (name "Net-(U2-CPH)") (class "Default")
      (node (ref "C6") (pin "2") (pinfunction "2_2") (pintype "passive"))
      (node (ref "U2") (pin "22") (pinfunction "CPH_22") (pintype "power_in"))
    )
    (net (code "44") (name "Net-(U2-CPL)") (class "Default")
      (node (ref "C6") (pin "1") (pinfunction "1_1") (pintype "passive"))
      (node (ref "U2") (pin "23") (pinfunction "CPL_23") (pintype "power_in"))
    )
    (net (code "45") (name "Net-(U2-DVDD)") (class "Default")
      (node (ref "C5") (pin "1") (pinfunction "1_1") (pintype "passive"))
      (node (ref "U2") (pin "1") (pinfunction "DVDD_1") (pintype "power_in"))
    )
    (net (code "46") (name "Net-(U2-VCP)") (class "Default")
      (node (ref "C7") (pin "1") (pinfunction "1_1") (pintype "passive"))
      (node (ref "U2") (pin "21") (pinfunction "VCP_21") (pintype "power_in"))
    )
    (net (code "47") (name "Net-(U3-CPH)") (class "Default")
      (node (ref "C14") (pin "2") (pinfunction "2_2") (pintype "passive"))
      (node (ref "U3") (pin "22") (pinfunction "CPH_22") (pintype "power_in"))
    )
    (net (code "48") (name "Net-(U3-CPL)") (class "Default")
      (node (ref "C14") (pin "1") (pinfunction "1_1") (pintype "passive"))
      (node (ref "U3") (pin "23") (pinfunction "CPL_23") (pintype "power_in"))
    )
    (net (code "49") (name "Net-(U3-DVDD)") (class "Default")
      (node (ref "C13") (pin "1") (pinfunction "1_1") (pintype "passive"))
      (node (ref "U3") (pin "1") (pinfunction "DVDD_1") (pintype "power_in"))
    )
    (net (code "50") (name "Net-(U3-VCP)") (class "Default")
      (node (ref "C15") (pin "1") (pinfunction "1_1") (pintype "passive"))
      (node (ref "U3") (pin "21") (pinfunction "VCP_21") (pintype "power_in"))
    )
    (net (code "51") (name "Net-(U4-CANH)") (class "Default")
      (node (ref "J6") (pin "3") (pinfunction "3_3") (pintype "passive"))
      (node (ref "U4") (pin "7") (pinfunction "CANH_7") (pintype "bidirectional"))
    )
    (net (code "52") (name "Net-(U4-CANL)") (class "Default")
      (node (ref "J6") (pin "2") (pinfunction "2_2") (pintype "passive"))
      (node (ref "U4") (pin "6") (pinfunction "CANL_6") (pintype "bidirectional"))
    )
    (net (code "53") (name "VM") (class "Default")
      (node (ref "C1") (pin "2") (pinfunction "A_2") (pintype "passive"))
      (node (ref "C10") (pin "1") (pinfunction "1_1") (pintype "passive"))
      (node (ref "C15") (pin "2") (pinfunction "2_2") (pintype "passive"))
      (node (ref "C18") (pin "1") (pinfunction "1_1") (pintype "passive"))
      (node (ref "C2") (pin "2") (pinfunction "A_2") (pintype "passive"))
      (node (ref "C20") (pin "1") (pinfunction "1_1") (pintype "passive"))
      (node (ref "C3") (pin "2") (pinfunction "A_2") (pintype "passive"))
      (node (ref "C4") (pin "2") (pinfunction "A_2") (pintype "passive"))
      (node (ref "C7") (pin "2") (pinfunction "2_2") (pintype "passive"))
      (node (ref "C8") (pin "1") (pinfunction "1_1") (pintype "passive"))
      (node (ref "D1") (pin "1") (pinfunction "C_1") (pintype "passive"))
      (node (ref "F1") (pin "2") (pinfunction "2_2") (pintype "passive"))
      (node (ref "U2") (pin "13") (pinfunction "VM_13") (pintype "power_in"))
      (node (ref "U2") (pin "20") (pinfunction "VM_20") (pintype "power_in"))
      (node (ref "U3") (pin "13") (pinfunction "VM_13") (pintype "power_in"))
      (node (ref "U3") (pin "20") (pinfunction "VM_20") (pintype "power_in"))
    )
    (net (code "54") (name "unconnected-(U1A-PA0-WKUP-Pad14)") (class "Default")
      (node (ref "U1") (pin "14") (pinfunction "PA0-WKUP_14") (pintype "bidirectional"))
    )
    (net (code "55") (name "unconnected-(U1A-PA1-Pad15)") (class "Default")
      (node (ref "U1") (pin "15") (pinfunction "PA1_15") (pintype "bidirectional"))
    )
    (net (code "56") (name "unconnected-(U1A-PA2-Pad16)") (class "Default")
      (node (ref "U1") (pin "16") (pinfunction "PA2_16") (pintype "bidirectional"))
    )
    (net (code "57") (name "unconnected-(U1A-PA4-Pad20)") (class "Default")
      (node (ref "U1") (pin "20") (pinfunction "PA4_20") (pintype "bidirectional"))
    )
    (net (code "58") (name "unconnected-(U1A-PA10-Pad43)") (class "Default")
      (node (ref "U1") (pin "43") (pinfunction "PA10_43") (pintype "bidirectional"))
    )
    (net (code "59") (name "unconnected-(U1A-PB2-Pad28)") (class "Default")
      (node (ref "U1") (pin "28") (pinfunction "PB2_28") (pintype "bidirectional"))
    )
    (net (code "60") (name "unconnected-(U1A-PB3-Pad55)") (class "Default")
      (node (ref "U1") (pin "55") (pinfunction "PB3_55") (pintype "bidirectional"))
    )
    (net (code "61") (name "unconnected-(U1A-PB8-Pad61)") (class "Default")
      (node (ref "U1") (pin "61") (pinfunction "PB8_61") (pintype "bidirectional"))
    )
    (net (code "62") (name "unconnected-(U1A-PB9-Pad62)") (class "Default")
      (node (ref "U1") (pin "62") (pinfunction "PB9_62") (pintype "bidirectional"))
    )
    (net (code "63") (name "unconnected-(U1A-PB14-Pad35)") (class "Default")
      (node (ref "U1") (pin "35") (pinfunction "PB14_35") (pintype "bidirectional"))
    )
    (net (code "64") (name "unconnected-(U1A-PC0-Pad8)") (class "Default")
      (node (ref "U1") (pin "8") (pinfunction "PC0_8") (pintype "bidirectional"))
    )
    (net (code "65") (name "unconnected-(U1A-PC1-Pad9)") (class "Default")
      (node (ref "U1") (pin "9") (pinfunction "PC1_9") (pintype "bidirectional"))
    )
    (net (code "66") (name "unconnected-(U1A-PC2-Pad10)") (class "Default")
      (node (ref "U1") (pin "10") (pinfunction "PC2_10") (pintype "bidirectional"))
    )
    (net (code "67") (name "unconnected-(U1A-PC3-Pad11)") (class "Default")
      (node (ref "U1") (pin "11") (pinfunction "PC3_11") (pintype "bidirectional"))
    )
    (net (code "68") (name "unconnected-(U1A-PC4-Pad24)") (class "Default")
      (node (ref "U1") (pin "24") (pinfunction "PC4_24") (pintype "bidirectional"))
    )
    (net (code "69") (name "unconnected-(U1A-PC8-Pad39)") (class "Default")
      (node (ref "U1") (pin "39") (pinfunction "PC8_39") (pintype "bidirectional"))
    )
    (net (code "70") (name "unconnected-(U1A-PC9-Pad40)") (class "Default")
      (node (ref "U1") (pin "40") (pinfunction "PC9_40") (pintype "bidirectional"))
    )
    (net (code "71") (name "unconnected-(U1A-PC11-Pad52)") (class "Default")
      (node (ref "U1") (pin "52") (pinfunction "PC11_52") (pintype "bidirectional"))
    )
    (net (code "72") (name "unconnected-(U1A-PC12-Pad53)") (class "Default")
      (node (ref "U1") (pin "53") (pinfunction "PC12_53") (pintype "bidirectional"))
    )
    (net (code "73") (name "unconnected-(U1A-PC13-TAMPER-RTC-Pad2)") (class "Default")
      (node (ref "U1") (pin "2") (pinfunction "PC13-TAMPER-RTC_2") (pintype "bidirectional"))
    )
    (net (code "74") (name "unconnected-(U1A-PC14-OSC32_IN-Pad3)") (class "Default")
      (node (ref "U1") (pin "3") (pinfunction "PC14-OSC32_IN_3") (pintype "bidirectional"))
    )
    (net (code "75") (name "unconnected-(U1A-PC15-OSC32_OUT-Pad4)") (class "Default")
      (node (ref "U1") (pin "4") (pinfunction "PC15-OSC32_OUT_4") (pintype "bidirectional"))
    )
    (net (code "76") (name "unconnected-(U1A-PD2-Pad54)") (class "Default")
      (node (ref "U1") (pin "54") (pinfunction "PD2_54") (pintype "bidirectional"))
    )
    (net (code "77") (name "unconnected-(U4-VREF-Pad5)") (class "Default")
      (node (ref "U4") (pin "5") (pinfunction "VREF_5") (pintype "output+no_connect"))
    )
  )
)
